# giraffe_mx5.net
KiCad netlist of a schematic drawn in EAGLE
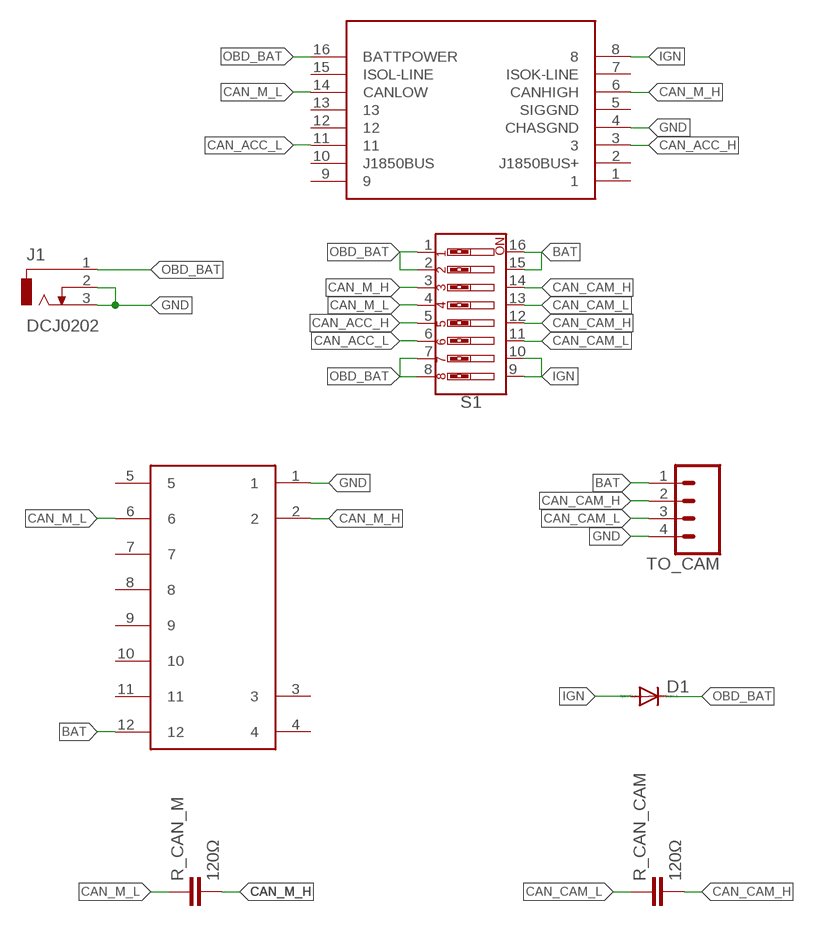
[diagram p0: schematic, sheet 1]

(export (version "E")
  (design (tool "Eeschema 10.0.6"))
  (components
    (comp (ref "D1")
      (value "DIODE-DO-214AC")
      (footprint "eagle-import:DO-214AC")
      (libsource (lib "eagle-import") (part "DIODE-DO-214AC"))
    )
    (comp (ref "J1")
      (value "DCJ0202")
      (footprint "eagle-import:DCJ0202")
      (libsource (lib "eagle-import") (part "DCJ0202"))
    )
    (comp (ref "OBD_II")
      (value "OBDII")
      (footprint "eagle-import:OBDII")
      (libsource (lib "eagle-import") (part "OBDII"))
    )
    (comp (ref "R_CAN_CAM")
      (value "120Ω")
      (footprint "eagle-import:C1206")
      (libsource (lib "eagle-import") (part "C-EUC1206"))
    )
    (comp (ref "R_CAN_M")
      (value "120Ω")
      (footprint "eagle-import:C1206")
      (libsource (lib "eagle-import") (part "C-EUC1206"))
    )
    (comp (ref "S1")
      (value "DIP-08-PTH")
      (footprint "eagle-import:DIPSWITCH-08")
      (libsource (lib "eagle-import") (part "DIP-08-PTH"))
    )
    (comp (ref "TO_CAM")
      (value "CONN_04LONGPADS")
      (footprint "eagle-import:1X04_LONGPADS")
      (libsource (lib "eagle-import") (part "CONN_04LONGPADS"))
    )
    (comp (ref "TO_CAR")
      (value "34826-8124")
      (footprint "eagle-import:34826-8124")
      (libsource (lib "eagle-import") (part "34826-8124"))
    )
  )
  (nets
    (net (code "1") (name "BAT") (class "Default")
      (node (ref "S1") (pin "15") (pinfunction "15_15") (pintype "passive"))
      (node (ref "S1") (pin "16") (pinfunction "16_16") (pintype "passive"))
      (node (ref "TO_CAM") (pin "1") (pinfunction "1_1") (pintype "passive"))
      (node (ref "TO_CAR") (pin "12") (pinfunction "12_12") (pintype "bidirectional"))
    )
    (net (code "2") (name "CAN_ACC_H") (class "Default")
      (node (ref "OBD_II") (pin "3") (pinfunction "3_3") (pintype "bidirectional"))
      (node (ref "S1") (pin "5") (pinfunction "5_5") (pintype "passive"))
    )
    (net (code "3") (name "CAN_ACC_L") (class "Default")
      (node (ref "OBD_II") (pin "11") (pinfunction "11_11") (pintype "bidirectional"))
      (node (ref "S1") (pin "6") (pinfunction "6_6") (pintype "passive"))
    )
    (net (code "4") (name "CAN_CAM_H") (class "Default")
      (node (ref "R_CAN_CAM") (pin "2") (pinfunction "2_2") (pintype "passive"))
      (node (ref "S1") (pin "12") (pinfunction "12_12") (pintype "passive"))
      (node (ref "S1") (pin "14") (pinfunction "14_14") (pintype "passive"))
      (node (ref "TO_CAM") (pin "2") (pinfunction "2_2") (pintype "passive"))
    )
    (net (code "5") (name "CAN_CAM_L") (class "Default")
      (node (ref "R_CAN_CAM") (pin "1") (pinfunction "1_1") (pintype "passive"))
      (node (ref "S1") (pin "11") (pinfunction "11_11") (pintype "passive"))
      (node (ref "S1") (pin "13") (pinfunction "13_13") (pintype "passive"))
      (node (ref "TO_CAM") (pin "3") (pinfunction "3_3") (pintype "passive"))
    )
    (net (code "6") (name "CAN_M_H") (class "Default")
      (node (ref "OBD_II") (pin "6") (pinfunction "CANHIGH_6") (pintype "bidirectional"))
      (node (ref "R_CAN_M") (pin "2") (pinfunction "2_2") (pintype "passive"))
      (node (ref "S1") (pin "3") (pinfunction "3_3") (pintype "passive"))
      (node (ref "TO_CAR") (pin "2") (pinfunction "2_2") (pintype "bidirectional"))
    )
    (net (code "7") (name "CAN_M_L") (class "Default")
      (node (ref "OBD_II") (pin "14") (pinfunction "CANLOW_14") (pintype "bidirectional"))
      (node (ref "R_CAN_M") (pin "1") (pinfunction "1_1") (pintype "passive"))
      (node (ref "S1") (pin "4") (pinfunction "4_4") (pintype "passive"))
      (node (ref "TO_CAR") (pin "6") (pinfunction "6_6") (pintype "bidirectional"))
    )
    (net (code "8") (name "GND") (class "Default")
      (node (ref "J1") (pin "2") (pinfunction "2_2") (pintype "passive"))
      (node (ref "J1") (pin "3") (pinfunction "3_3") (pintype "passive"))
      (node (ref "OBD_II") (pin "4") (pinfunction "CHASGND_4") (pintype "bidirectional"))
      (node (ref "TO_CAM") (pin "4") (pinfunction "4_4") (pintype "passive"))
      (node (ref "TO_CAR") (pin "1") (pinfunction "1_1") (pintype "bidirectional"))
    )
    (net (code "9") (name "IGN") (class "Default")
      (node (ref "D1") (pin "A") (pinfunction "A_A") (pintype "passive"))
      (node (ref "OBD_II") (pin "8") (pinfunction "8_8") (pintype "bidirectional"))
      (node (ref "S1") (pin "10") (pinfunction "10_10") (pintype "passive"))
      (node (ref "S1") (pin "9") (pinfunction "9_9") (pintype "passive"))
    )
    (net (code "10") (name "OBD_BAT") (class "Default")
      (node (ref "D1") (pin "C") (pinfunction "C_C") (pintype "passive"))
      (node (ref "J1") (pin "1") (pinfunction "1_1") (pintype "passive"))
      (node (ref "OBD_II") (pin "16") (pinfunction "BATTPOWER_16") (pintype "bidirectional"))
      (node (ref "S1") (pin "1") (pinfunction "1_1") (pintype "passive"))
      (node (ref "S1") (pin "2") (pinfunction "2_2") (pintype "passive"))
      (node (ref "S1") (pin "7") (pinfunction "7_7") (pintype "passive"))
      (node (ref "S1") (pin "8") (pinfunction "8_8") (pintype "passive"))
    )
    (net (code "11") (name "unconnected-(OBD_II-ISOK-LINE-Pad7)") (class "Default")
      (node (ref "OBD_II") (pin "7") (pinfunction "ISOK-LINE_7") (pintype "bidirectional"))
    )
    (net (code "12") (name "unconnected-(OBD_II-ISOL-LINE-Pad15)") (class "Default")
      (node (ref "OBD_II") (pin "15") (pinfunction "ISOL-LINE_15") (pintype "bidirectional"))
    )
    (net (code "13") (name "unconnected-(OBD_II-J1850BUS+-Pad2)") (class "Default")
      (node (ref "OBD_II") (pin "2") (pinfunction "J1850BUS+_2") (pintype "bidirectional"))
    )
    (net (code "14") (name "unconnected-(OBD_II-J1850BUS-Pad10)") (class "Default")
      (node (ref "OBD_II") (pin "10") (pinfunction "J1850BUS_10") (pintype "bidirectional"))
    )
    (net (code "15") (name "unconnected-(OBD_II-Pad1)") (class "Default")
      (node (ref "OBD_II") (pin "1") (pinfunction "1_1") (pintype "bidirectional"))
    )
    (net (code "16") (name "unconnected-(OBD_II-Pad9)") (class "Default")
      (node (ref "OBD_II") (pin "9") (pinfunction "9_9") (pintype "bidirectional"))
    )
    (net (code "17") (name "unconnected-(OBD_II-Pad12)") (class "Default")
      (node (ref "OBD_II") (pin "12") (pinfunction "12_12") (pintype "bidirectional"))
    )
    (net (code "18") (name "unconnected-(OBD_II-Pad13)") (class "Default")
      (node (ref "OBD_II") (pin "13") (pinfunction "13_13") (pintype "bidirectional"))
    )
    (net (code "19") (name "unconnected-(OBD_II-SIGGND-Pad5)") (class "Default")
      (node (ref "OBD_II") (pin "5") (pinfunction "SIGGND_5") (pintype "bidirectional"))
    )
    (net (code "20") (name "unconnected-(TO_CAR-Pad3)") (class "Default")
      (node (ref "TO_CAR") (pin "3") (pinfunction "3_3") (pintype "bidirectional"))
    )
    (net (code "21") (name "unconnected-(TO_CAR-Pad4)") (class "Default")
      (node (ref "TO_CAR") (pin "4") (pinfunction "4_4") (pintype "bidirectional"))
    )
    (net (code "22") (name "unconnected-(TO_CAR-Pad5)") (class "Default")
      (node (ref "TO_CAR") (pin "5") (pinfunction "5_5") (pintype "bidirectional"))
    )
    (net (code "23") (name "unconnected-(TO_CAR-Pad7)") (class "Default")
      (node (ref "TO_CAR") (pin "7") (pinfunction "7_7") (pintype "bidirectional"))
    )
    (net (code "24") (name "unconnected-(TO_CAR-Pad8)") (class "Default")
      (node (ref "TO_CAR") (pin "8") (pinfunction "8_8") (pintype "bidirectional"))
    )
    (net (code "25") (name "unconnected-(TO_CAR-Pad9)") (class "Default")
      (node (ref "TO_CAR") (pin "9") (pinfunction "9_9") (pintype "bidirectional"))
    )
    (net (code "26") (name "unconnected-(TO_CAR-Pad10)") (class "Default")
      (node (ref "TO_CAR") (pin "10") (pinfunction "10_10") (pintype "bidirectional"))
    )
    (net (code "27") (name "unconnected-(TO_CAR-Pad11)") (class "Default")
      (node (ref "TO_CAR") (pin "11") (pinfunction "11_11") (pintype "bidirectional"))
    )
  )
)
